# test2.net
KiCad netlist of a schematic drawn in EAGLE
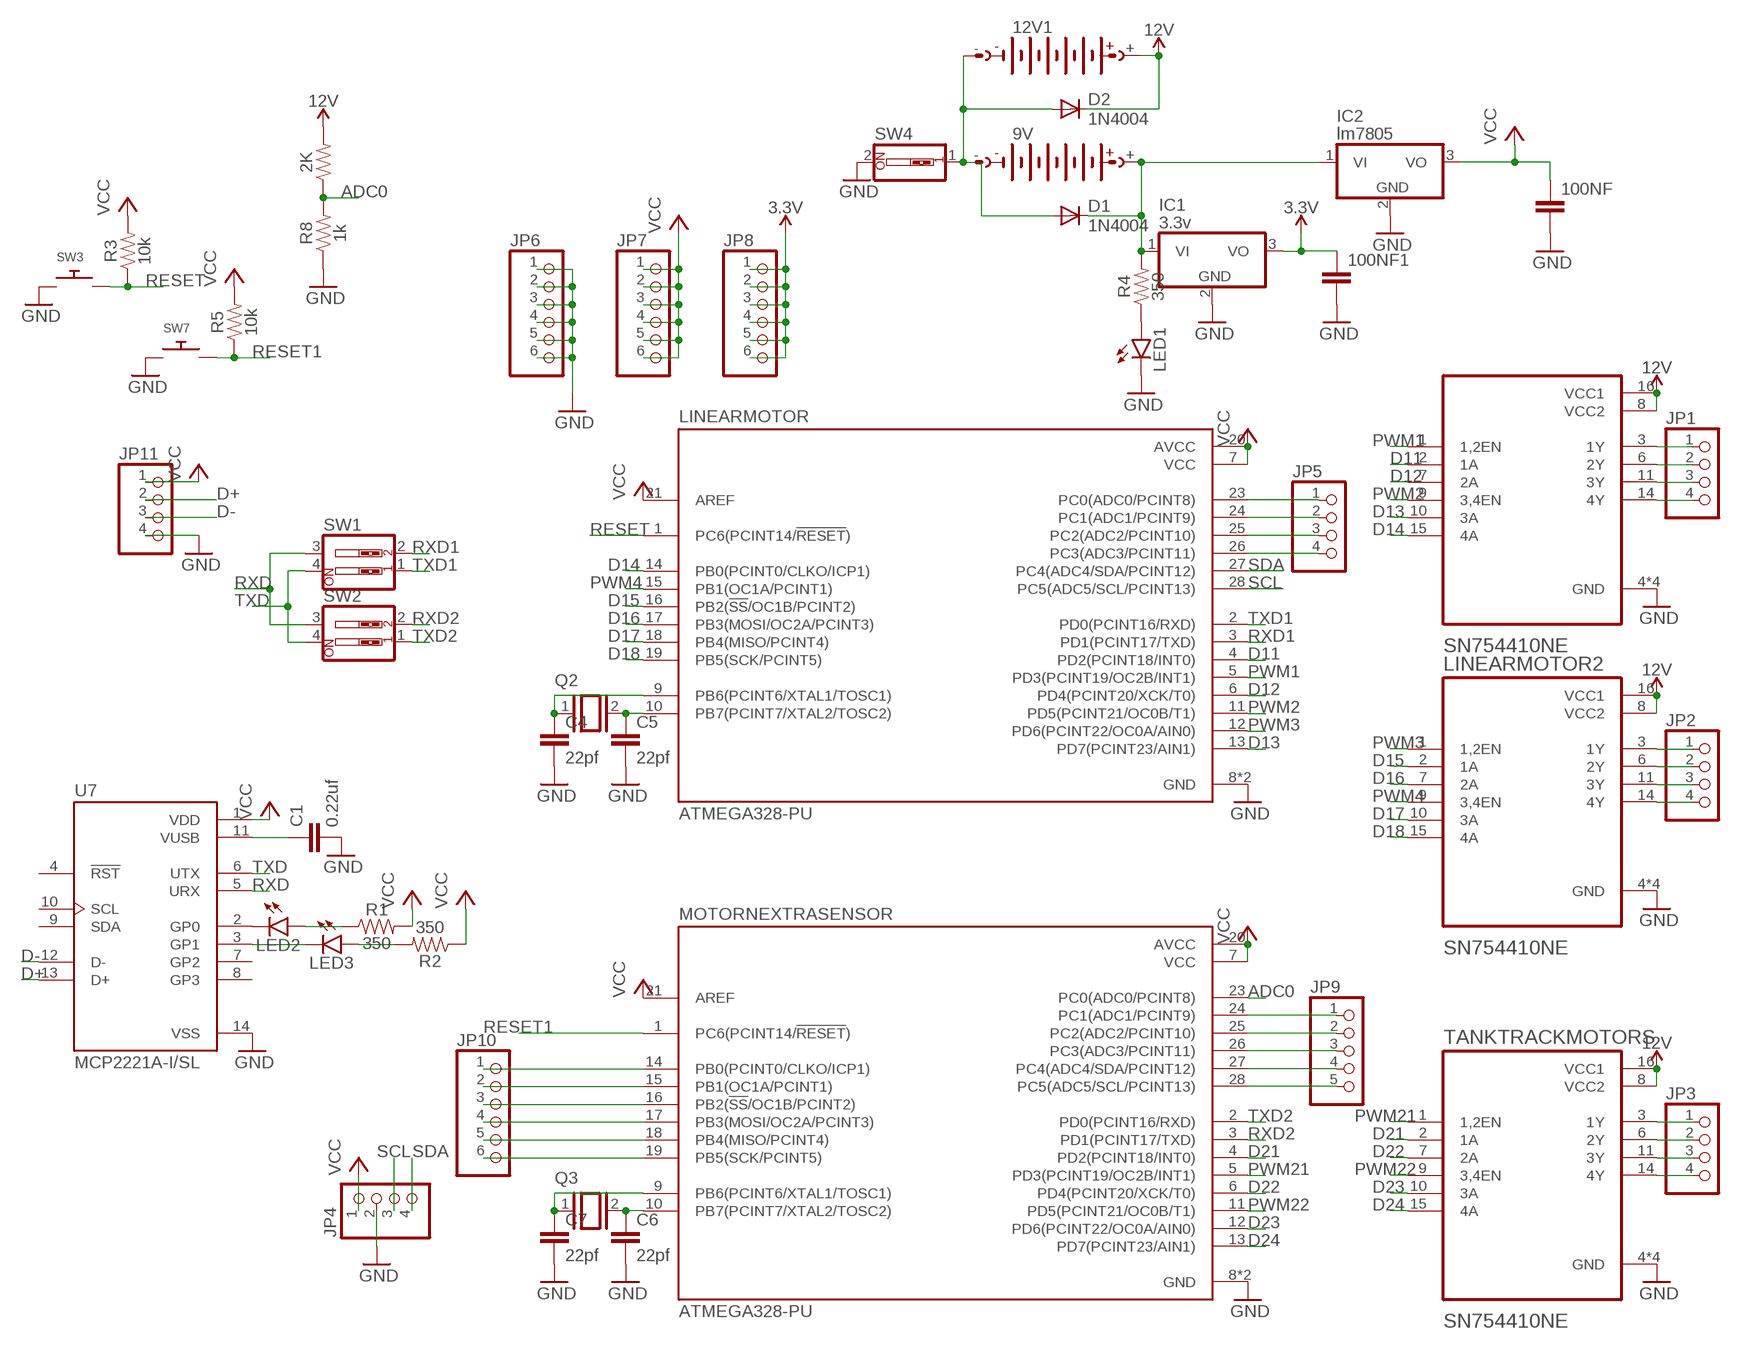
[diagram p0: schematic, sheet 1]

(export (version "E")
  (design (tool "Eeschema 10.0.6"))
  (components
    (comp (ref "2K")
      (value "2k")
      (footprint "eagle-import:AXIAL-0.3")
      (libsource (lib "eagle-import") (part "1KOHM-HORIZ-1/4W-1%"))
    )
    (comp (ref "9V")
      (value "AB9V")
      (footprint "eagle-import:AB9V")
      (libsource (lib "eagle-import") (part "AB9V"))
    )
    (comp (ref "12V1")
      (value "AB9V")
      (footprint "eagle-import:AB9V")
      (libsource (lib "eagle-import") (part "AB9V"))
    )
    (comp (ref "100NF")
      (value "330nF")
      (footprint "eagle-import:CAP-PTH-10MM")
      (libsource (lib "eagle-import") (part "10NF-PTH-10MM-10000V-1-%"))
    )
    (comp (ref "100NF1")
      (value "330nF")
      (footprint "eagle-import:CAP-PTH-10MM")
      (libsource (lib "eagle-import") (part "10NF-PTH-10MM-10000V-1-%"))
    )
    (comp (ref "C1")
      (value "0.22uf")
      (footprint "eagle-import:CAP-PTH-10MM")
      (libsource (lib "eagle-import") (part "10NF-PTH-10MM-10000V-1-%"))
    )
    (comp (ref "C4")
      (value "22pf")
      (footprint "eagle-import:CAP-PTH-10MM")
      (libsource (lib "eagle-import") (part "10NF-PTH-10MM-10000V-1-%"))
    )
    (comp (ref "C5")
      (value "22pf")
      (footprint "eagle-import:CAP-PTH-10MM")
      (libsource (lib "eagle-import") (part "10NF-PTH-10MM-10000V-1-%"))
    )
    (comp (ref "C6")
      (value "22pf")
      (footprint "eagle-import:CAP-PTH-10MM")
      (libsource (lib "eagle-import") (part "10NF-PTH-10MM-10000V-1-%"))
    )
    (comp (ref "C7")
      (value "22pf")
      (footprint "eagle-import:CAP-PTH-10MM")
      (libsource (lib "eagle-import") (part "10NF-PTH-10MM-10000V-1-%"))
    )
    (comp (ref "D1")
      (value "1N4004")
      (footprint "eagle-import:DO41-10")
      (libsource (lib "eagle-import") (part "1N4004"))
    )
    (comp (ref "D2")
      (value "1N4004")
      (footprint "eagle-import:DO41-10")
      (libsource (lib "eagle-import") (part "1N4004"))
    )
    (comp (ref "IC1")
      (value "3.3v")
      (footprint "eagle-import:TO220V")
      (libsource (lib "eagle-import") (part "78TV8"))
    )
    (comp (ref "IC2")
      (value "lm7805")
      (footprint "eagle-import:TO220V")
      (libsource (lib "eagle-import") (part "78TV8"))
    )
    (comp (ref "JP1")
      (value "PINHD-1X4")
      (footprint "eagle-import:1X04")
      (libsource (lib "eagle-import") (part "PINHD-1X4"))
    )
    (comp (ref "JP2")
      (value "PINHD-1X4")
      (footprint "eagle-import:1X04")
      (libsource (lib "eagle-import") (part "PINHD-1X4"))
    )
    (comp (ref "JP3")
      (value "PINHD-1X4")
      (footprint "eagle-import:1X04")
      (libsource (lib "eagle-import") (part "PINHD-1X4"))
    )
    (comp (ref "JP4")
      (value "PINHD-1X4")
      (footprint "eagle-import:1X04")
      (libsource (lib "eagle-import") (part "PINHD-1X4"))
    )
    (comp (ref "JP5")
      (value "PINHD-1X4")
      (footprint "eagle-import:1X04")
      (libsource (lib "eagle-import") (part "PINHD-1X4"))
    )
    (comp (ref "JP6")
      (value "PINHD-1X6")
      (footprint "eagle-import:1X06")
      (libsource (lib "eagle-import") (part "PINHD-1X6"))
    )
    (comp (ref "JP7")
      (value "PINHD-1X6")
      (footprint "eagle-import:1X06")
      (libsource (lib "eagle-import") (part "PINHD-1X6"))
    )
    (comp (ref "JP8")
      (value "PINHD-1X6")
      (footprint "eagle-import:1X06")
      (libsource (lib "eagle-import") (part "PINHD-1X6"))
    )
    (comp (ref "JP9")
      (value "PINHD-1X5")
      (footprint "eagle-import:1X05")
      (libsource (lib "eagle-import") (part "PINHD-1X5"))
    )
    (comp (ref "JP10")
      (value "PINHD-1X6")
      (footprint "eagle-import:1X06")
      (libsource (lib "eagle-import") (part "PINHD-1X6"))
    )
    (comp (ref "JP11")
      (value "PINHD-1X4")
      (footprint "eagle-import:1X04")
      (libsource (lib "eagle-import") (part "PINHD-1X4"))
    )
    (comp (ref "LED1")
      (value "LED3MM")
      (footprint "eagle-import:LED3MM")
      (libsource (lib "eagle-import") (part "LED3MM"))
    )
    (comp (ref "LED2")
      (value "LED3MM")
      (footprint "eagle-import:LED3MM")
      (libsource (lib "eagle-import") (part "LED3MM"))
    )
    (comp (ref "LED3")
      (value "LED3MM")
      (footprint "eagle-import:LED3MM")
      (libsource (lib "eagle-import") (part "LED3MM"))
    )
    (comp (ref "LINEARMOTOR")
      (value "ATMEGA328-PU")
      (footprint "eagle-import:DIP787W46P254L3467H508Q28")
      (fields (field (name "MF") "Microchip Technology"))
      (libsource (lib "eagle-import") (part "ATMEGA328-PU"))
    )
    (comp (ref "LINEARMOTOR1")
      (value "SN754410NE")
      (footprint "eagle-import:DIP762W45P254L1980H508Q16")
      (fields (field (name "MF") "Texas Instruments"))
      (libsource (lib "eagle-import") (part "SN754410NE"))
    )
    (comp (ref "LINEARMOTOR2")
      (value "SN754410NE")
      (footprint "eagle-import:DIP762W45P254L1980H508Q16")
      (fields (field (name "MF") "Texas Instruments"))
      (libsource (lib "eagle-import") (part "SN754410NE"))
    )
    (comp (ref "MOTORNEXTRASENSOR")
      (value "ATMEGA328-PU")
      (footprint "eagle-import:DIP787W46P254L3467H508Q28")
      (fields (field (name "MF") "Microchip Technology"))
      (libsource (lib "eagle-import") (part "ATMEGA328-PU"))
    )
    (comp (ref "Q2")
      (value "XTAL/S")
      (footprint "eagle-import:QS")
      (libsource (lib "eagle-import") (part "XTAL/S"))
    )
    (comp (ref "Q3")
      (value "XTAL/S")
      (footprint "eagle-import:QS")
      (libsource (lib "eagle-import") (part "XTAL/S"))
    )
    (comp (ref "R1")
      (value "350")
      (footprint "eagle-import:AXIAL-0.3")
      (libsource (lib "eagle-import") (part "1KOHM-HORIZ-1/4W-1%"))
    )
    (comp (ref "R2")
      (value "350")
      (footprint "eagle-import:AXIAL-0.3")
      (libsource (lib "eagle-import") (part "1KOHM-HORIZ-1/4W-1%"))
    )
    (comp (ref "R3")
      (value "10k")
      (footprint "eagle-import:AXIAL-0.3")
      (libsource (lib "eagle-import") (part "10KOHM-HORIZ-1/4W-1%"))
    )
    (comp (ref "R4")
      (value "350")
      (footprint "eagle-import:AXIAL-0.3")
      (libsource (lib "eagle-import") (part "1KOHM-HORIZ-1/4W-1%"))
    )
    (comp (ref "R5")
      (value "10k")
      (footprint "eagle-import:AXIAL-0.3")
      (libsource (lib "eagle-import") (part "10KOHM-HORIZ-1/4W-1%"))
    )
    (comp (ref "R8")
      (value "1k")
      (footprint "eagle-import:AXIAL-0.3")
      (libsource (lib "eagle-import") (part "1KOHM-HORIZ-1/4W-1%"))
    )
    (comp (ref "SW1")
      (value "SW_DIP-2")
      (footprint "eagle-import:EDG-02")
      (libsource (lib "eagle-import") (part "SW_DIP-2"))
    )
    (comp (ref "SW2")
      (value "SW_DIP-2")
      (footprint "eagle-import:EDG-02")
      (libsource (lib "eagle-import") (part "SW_DIP-2"))
    )
    (comp (ref "SW3")
      (value "SWITCH_PUSHBUTTONEVQ-PE")
      (footprint "eagle-import:TACT_PANA-EVQ")
      (libsource (lib "eagle-import") (part "SWITCH_PUSHBUTTONEVQ-PE"))
    )
    (comp (ref "SW4")
      (value "SW_DIP-1")
      (footprint "eagle-import:EDG-01")
      (libsource (lib "eagle-import") (part "SW_DIP-1"))
    )
    (comp (ref "SW7")
      (value "SWITCH_PUSHBUTTONEVQ-PE")
      (footprint "eagle-import:TACT_PANA-EVQ")
      (libsource (lib "eagle-import") (part "SWITCH_PUSHBUTTONEVQ-PE"))
    )
    (comp (ref "TANKTRACKMOTORS")
      (value "SN754410NE")
      (footprint "eagle-import:DIP762W45P254L1980H508Q16")
      (fields (field (name "MF") "Texas Instruments"))
      (libsource (lib "eagle-import") (part "SN754410NE"))
    )
    (comp (ref "U7")
      (value "MCP2221A-I/SL")
      (footprint "eagle-import:SOIC127P600X175-14N")
      (fields (field (name "MF") "Microchip"))
      (libsource (lib "eagle-import") (part "MCP2221A-I/SL"))
    )
  )
  (nets
    (net (code "1") (name "/ADC0") (class "Default")
      (node (ref "2K") (pin "P$1") (pinfunction "1_P$1") (pintype "passive"))
      (node (ref "MOTORNEXTRASENSOR") (pin "23") (pinfunction "PC0(ADC0/PCINT8)_23") (pintype "bidirectional"))
      (node (ref "R8") (pin "P$2") (pinfunction "2_P$2") (pintype "passive"))
    )
    (net (code "2") (name "/D+") (class "Default")
      (node (ref "JP11") (pin "2") (pinfunction "2_2") (pintype "passive"))
      (node (ref "U7") (pin "13") (pinfunction "D+_13") (pintype "bidirectional"))
    )
    (net (code "3") (name "/D-") (class "Default")
      (node (ref "JP11") (pin "3") (pinfunction "3_3") (pintype "passive"))
      (node (ref "U7") (pin "12") (pinfunction "D-_12") (pintype "bidirectional"))
    )
    (net (code "4") (name "/D11") (class "Default")
      (node (ref "LINEARMOTOR") (pin "4") (pinfunction "PD2(PCINT18/INT0)_4") (pintype "bidirectional"))
      (node (ref "LINEARMOTOR1") (pin "2") (pinfunction "1A_2") (pintype "input"))
    )
    (net (code "5") (name "/D12") (class "Default")
      (node (ref "LINEARMOTOR") (pin "6") (pinfunction "PD4(PCINT20/XCK/T0)_6") (pintype "bidirectional"))
      (node (ref "LINEARMOTOR1") (pin "7") (pinfunction "2A_7") (pintype "input"))
    )
    (net (code "6") (name "/D13") (class "Default")
      (node (ref "LINEARMOTOR") (pin "13") (pinfunction "PD7(PCINT23/AIN1)_13") (pintype "bidirectional"))
      (node (ref "LINEARMOTOR1") (pin "10") (pinfunction "3A_10") (pintype "input"))
    )
    (net (code "7") (name "/D14") (class "Default")
      (node (ref "LINEARMOTOR") (pin "14") (pinfunction "PB0(PCINT0/CLKO/ICP1)_14") (pintype "bidirectional"))
      (node (ref "LINEARMOTOR1") (pin "15") (pinfunction "4A_15") (pintype "input"))
    )
    (net (code "8") (name "/D15") (class "Default")
      (node (ref "LINEARMOTOR") (pin "16") (pinfunction "PB2(~{SS}/OC1B/PCINT2)_16") (pintype "bidirectional"))
      (node (ref "LINEARMOTOR2") (pin "2") (pinfunction "1A_2") (pintype "input"))
    )
    (net (code "9") (name "/D16") (class "Default")
      (node (ref "LINEARMOTOR") (pin "17") (pinfunction "PB3(MOSI/OC2A/PCINT3)_17") (pintype "bidirectional"))
      (node (ref "LINEARMOTOR2") (pin "7") (pinfunction "2A_7") (pintype "input"))
    )
    (net (code "10") (name "/D17") (class "Default")
      (node (ref "LINEARMOTOR") (pin "18") (pinfunction "PB4(MISO/PCINT4)_18") (pintype "bidirectional"))
      (node (ref "LINEARMOTOR2") (pin "10") (pinfunction "3A_10") (pintype "input"))
    )
    (net (code "11") (name "/D18") (class "Default")
      (node (ref "LINEARMOTOR") (pin "19") (pinfunction "PB5(SCK/PCINT5)_19") (pintype "bidirectional"))
      (node (ref "LINEARMOTOR2") (pin "15") (pinfunction "4A_15") (pintype "input"))
    )
    (net (code "12") (name "/D21") (class "Default")
      (node (ref "MOTORNEXTRASENSOR") (pin "4") (pinfunction "PD2(PCINT18/INT0)_4") (pintype "bidirectional"))
      (node (ref "TANKTRACKMOTORS") (pin "2") (pinfunction "1A_2") (pintype "input"))
    )
    (net (code "13") (name "/D22") (class "Default")
      (node (ref "MOTORNEXTRASENSOR") (pin "6") (pinfunction "PD4(PCINT20/XCK/T0)_6") (pintype "bidirectional"))
      (node (ref "TANKTRACKMOTORS") (pin "7") (pinfunction "2A_7") (pintype "input"))
    )
    (net (code "14") (name "/D23") (class "Default")
      (node (ref "MOTORNEXTRASENSOR") (pin "12") (pinfunction "PD6(PCINT22/OC0A/AIN0)_12") (pintype "bidirectional"))
      (node (ref "TANKTRACKMOTORS") (pin "10") (pinfunction "3A_10") (pintype "input"))
    )
    (net (code "15") (name "/D24") (class "Default")
      (node (ref "MOTORNEXTRASENSOR") (pin "13") (pinfunction "PD7(PCINT23/AIN1)_13") (pintype "bidirectional"))
      (node (ref "TANKTRACKMOTORS") (pin "15") (pinfunction "4A_15") (pintype "input"))
    )
    (net (code "16") (name "/PWM1") (class "Default")
      (node (ref "LINEARMOTOR") (pin "5") (pinfunction "PD3(PCINT19/OC2B/INT1)_5") (pintype "bidirectional"))
      (node (ref "LINEARMOTOR1") (pin "1") (pinfunction "1,2EN_1") (pintype "input"))
    )
    (net (code "17") (name "/PWM2") (class "Default")
      (node (ref "LINEARMOTOR") (pin "11") (pinfunction "PD5(PCINT21/OC0B/T1)_11") (pintype "bidirectional"))
      (node (ref "LINEARMOTOR1") (pin "9") (pinfunction "3,4EN_9") (pintype "input"))
    )
    (net (code "18") (name "/PWM3") (class "Default")
      (node (ref "LINEARMOTOR") (pin "12") (pinfunction "PD6(PCINT22/OC0A/AIN0)_12") (pintype "bidirectional"))
      (node (ref "LINEARMOTOR2") (pin "1") (pinfunction "1,2EN_1") (pintype "input"))
    )
    (net (code "19") (name "/PWM4") (class "Default")
      (node (ref "LINEARMOTOR") (pin "15") (pinfunction "PB1(OC1A/PCINT1)_15") (pintype "bidirectional"))
      (node (ref "LINEARMOTOR2") (pin "9") (pinfunction "3,4EN_9") (pintype "input"))
    )
    (net (code "20") (name "/PWM21") (class "Default")
      (node (ref "MOTORNEXTRASENSOR") (pin "5") (pinfunction "PD3(PCINT19/OC2B/INT1)_5") (pintype "bidirectional"))
      (node (ref "TANKTRACKMOTORS") (pin "1") (pinfunction "1,2EN_1") (pintype "input"))
    )
    (net (code "21") (name "/PWM22") (class "Default")
      (node (ref "MOTORNEXTRASENSOR") (pin "11") (pinfunction "PD5(PCINT21/OC0B/T1)_11") (pintype "bidirectional"))
      (node (ref "TANKTRACKMOTORS") (pin "9") (pinfunction "3,4EN_9") (pintype "input"))
    )
    (net (code "22") (name "/RESET") (class "Default")
      (node (ref "LINEARMOTOR") (pin "1") (pinfunction "PC6(PCINT14/~{RESET})_1") (pintype "bidirectional"))
      (node (ref "R3") (pin "P$1") (pinfunction "1_P$1") (pintype "passive"))
      (node (ref "SW3") (pin "P$2") (pinfunction "P$2_P$2") (pintype "passive"))
    )
    (net (code "23") (name "/RESET1") (class "Default")
      (node (ref "MOTORNEXTRASENSOR") (pin "1") (pinfunction "PC6(PCINT14/~{RESET})_1") (pintype "bidirectional"))
      (node (ref "R5") (pin "P$1") (pinfunction "1_P$1") (pintype "passive"))
      (node (ref "SW7") (pin "P$2") (pinfunction "P$2_P$2") (pintype "passive"))
    )
    (net (code "24") (name "/RXD") (class "Default")
      (node (ref "SW1") (pin "3") (pinfunction "3_3") (pintype "passive"))
      (node (ref "SW2") (pin "3") (pinfunction "3_3") (pintype "passive"))
      (node (ref "U7") (pin "5") (pinfunction "URX_5") (pintype "input"))
    )
    (net (code "25") (name "/RXD1") (class "Default")
      (node (ref "LINEARMOTOR") (pin "3") (pinfunction "PD1(PCINT17/TXD)_3") (pintype "bidirectional"))
      (node (ref "SW1") (pin "2") (pinfunction "2_2") (pintype "passive"))
    )
    (net (code "26") (name "/RXD2") (class "Default")
      (node (ref "MOTORNEXTRASENSOR") (pin "3") (pinfunction "PD1(PCINT17/TXD)_3") (pintype "bidirectional"))
      (node (ref "SW2") (pin "2") (pinfunction "2_2") (pintype "passive"))
    )
    (net (code "27") (name "/SCL") (class "Default")
      (node (ref "JP4") (pin "3") (pinfunction "3_3") (pintype "passive"))
      (node (ref "LINEARMOTOR") (pin "28") (pinfunction "PC5(ADC5/SCL/PCINT13)_28") (pintype "bidirectional"))
    )
    (net (code "28") (name "/SDA") (class "Default")
      (node (ref "JP4") (pin "4") (pinfunction "4_4") (pintype "passive"))
      (node (ref "LINEARMOTOR") (pin "27") (pinfunction "PC4(ADC4/SDA/PCINT12)_27") (pintype "bidirectional"))
    )
    (net (code "29") (name "/TXD") (class "Default")
      (node (ref "SW1") (pin "4") (pinfunction "4_4") (pintype "passive"))
      (node (ref "SW2") (pin "4") (pinfunction "4_4") (pintype "passive"))
      (node (ref "U7") (pin "6") (pinfunction "UTX_6") (pintype "output"))
    )
    (net (code "30") (name "/TXD1") (class "Default")
      (node (ref "LINEARMOTOR") (pin "2") (pinfunction "PD0(PCINT16/RXD)_2") (pintype "bidirectional"))
      (node (ref "SW1") (pin "1") (pinfunction "1_1") (pintype "passive"))
    )
    (net (code "31") (name "/TXD2") (class "Default")
      (node (ref "MOTORNEXTRASENSOR") (pin "2") (pinfunction "PD0(PCINT16/RXD)_2") (pintype "bidirectional"))
      (node (ref "SW2") (pin "1") (pinfunction "1_1") (pintype "passive"))
    )
    (net (code "32") (name "3.3V") (class "Default")
      (node (ref "100NF1") (pin "1") (pinfunction "1_1") (pintype "passive"))
      (node (ref "IC1") (pin "3") (pinfunction "VO_3") (pintype "passive"))
      (node (ref "JP8") (pin "1") (pinfunction "1_1") (pintype "passive"))
      (node (ref "JP8") (pin "2") (pinfunction "2_2") (pintype "passive"))
      (node (ref "JP8") (pin "3") (pinfunction "3_3") (pintype "passive"))
      (node (ref "JP8") (pin "4") (pinfunction "4_4") (pintype "passive"))
      (node (ref "JP8") (pin "5") (pinfunction "5_5") (pintype "passive"))
      (node (ref "JP8") (pin "6") (pinfunction "6_6") (pintype "passive"))
    )
    (net (code "33") (name "12V") (class "Default")
      (node (ref "12V1") (pin "+") (pinfunction "+_+") (pintype "passive"))
      (node (ref "2K") (pin "P$2") (pinfunction "2_P$2") (pintype "passive"))
      (node (ref "D2") (pin "C") (pinfunction "C_C") (pintype "passive"))
      (node (ref "LINEARMOTOR1") (pin "16") (pinfunction "VCC1_16") (pintype "power_in"))
      (node (ref "LINEARMOTOR1") (pin "8") (pinfunction "VCC2_8") (pintype "power_in"))
      (node (ref "LINEARMOTOR2") (pin "16") (pinfunction "VCC1_16") (pintype "power_in"))
      (node (ref "LINEARMOTOR2") (pin "8") (pinfunction "VCC2_8") (pintype "power_in"))
      (node (ref "TANKTRACKMOTORS") (pin "16") (pinfunction "VCC1_16") (pintype "power_in"))
      (node (ref "TANKTRACKMOTORS") (pin "8") (pinfunction "VCC2_8") (pintype "power_in"))
    )
    (net (code "34") (name "GND") (class "Default")
      (node (ref "100NF") (pin "2") (pinfunction "2_2") (pintype "passive"))
      (node (ref "100NF1") (pin "2") (pinfunction "2_2") (pintype "passive"))
      (node (ref "C1") (pin "2") (pinfunction "2_2") (pintype "passive"))
      (node (ref "C4") (pin "2") (pinfunction "2_2") (pintype "passive"))
      (node (ref "C5") (pin "2") (pinfunction "2_2") (pintype "passive"))
      (node (ref "C6") (pin "2") (pinfunction "2_2") (pintype "passive"))
      (node (ref "C7") (pin "2") (pinfunction "2_2") (pintype "passive"))
      (node (ref "IC1") (pin "2") (pinfunction "GND_2") (pintype "passive"))
      (node (ref "IC2") (pin "2") (pinfunction "GND_2") (pintype "passive"))
      (node (ref "JP11") (pin "4") (pinfunction "4_4") (pintype "passive"))
      (node (ref "JP4") (pin "2") (pinfunction "2_2") (pintype "passive"))
      (node (ref "JP6") (pin "1") (pinfunction "1_1") (pintype "passive"))
      (node (ref "JP6") (pin "2") (pinfunction "2_2") (pintype "passive"))
      (node (ref "JP6") (pin "3") (pinfunction "3_3") (pintype "passive"))
      (node (ref "JP6") (pin "4") (pinfunction "4_4") (pintype "passive"))
      (node (ref "JP6") (pin "5") (pinfunction "5_5") (pintype "passive"))
      (node (ref "JP6") (pin "6") (pinfunction "6_6") (pintype "passive"))
      (node (ref "LED1") (pin "K") (pinfunction "C_K") (pintype "passive"))
      (node (ref "LINEARMOTOR") (pin "22") (pinfunction "GND_22") (pintype "power_in"))
      (node (ref "LINEARMOTOR") (pin "8") (pinfunction "GND_8") (pintype "power_in"))
      (node (ref "LINEARMOTOR1") (pin "12") (pinfunction "GND_12") (pintype "power_in"))
      (node (ref "LINEARMOTOR1") (pin "13") (pinfunction "GND_13") (pintype "power_in"))
      (node (ref "LINEARMOTOR1") (pin "4") (pinfunction "GND_4") (pintype "power_in"))
      (node (ref "LINEARMOTOR1") (pin "5") (pinfunction "GND_5") (pintype "power_in"))
      (node (ref "LINEARMOTOR2") (pin "12") (pinfunction "GND_12") (pintype "power_in"))
      (node (ref "LINEARMOTOR2") (pin "13") (pinfunction "GND_13") (pintype "power_in"))
      (node (ref "LINEARMOTOR2") (pin "4") (pinfunction "GND_4") (pintype "power_in"))
      (node (ref "LINEARMOTOR2") (pin "5") (pinfunction "GND_5") (pintype "power_in"))
      (node (ref "MOTORNEXTRASENSOR") (pin "22") (pinfunction "GND_22") (pintype "power_in"))
      (node (ref "MOTORNEXTRASENSOR") (pin "8") (pinfunction "GND_8") (pintype "power_in"))
      (node (ref "R8") (pin "P$1") (pinfunction "1_P$1") (pintype "passive"))
      (node (ref "SW3") (pin "P$1") (pinfunction "P$1_P$1") (pintype "passive"))
      (node (ref "SW4") (pin "2") (pinfunction "2_2") (pintype "passive"))
      (node (ref "SW7") (pin "P$1") (pinfunction "P$1_P$1") (pintype "passive"))
      (node (ref "TANKTRACKMOTORS") (pin "12") (pinfunction "GND_12") (pintype "power_in"))
      (node (ref "TANKTRACKMOTORS") (pin "13") (pinfunction "GND_13") (pintype "power_in"))
      (node (ref "TANKTRACKMOTORS") (pin "4") (pinfunction "GND_4") (pintype "power_in"))
      (node (ref "TANKTRACKMOTORS") (pin "5") (pinfunction "GND_5") (pintype "power_in"))
      (node (ref "U7") (pin "14") (pinfunction "VSS_14") (pintype "power_in"))
    )
    (net (code "35") (name "Net-(12V1-Pad-)") (class "Default")
      (node (ref "12V1") (pin "-") (pinfunction "-_-") (pintype "passive"))
      (node (ref "9V") (pin "-") (pinfunction "-_-") (pintype "passive"))
      (node (ref "D1") (pin "A") (pinfunction "A_A") (pintype "passive"))
      (node (ref "D2") (pin "A") (pinfunction "A_A") (pintype "passive"))
      (node (ref "SW4") (pin "1") (pinfunction "1_1") (pintype "passive"))
    )
    (net (code "36") (name "Net-(IC1-VI)") (class "Default")
      (node (ref "9V") (pin "+") (pinfunction "+_+") (pintype "passive"))
      (node (ref "D1") (pin "C") (pinfunction "C_C") (pintype "passive"))
      (node (ref "IC1") (pin "1") (pinfunction "VI_1") (pintype "input"))
      (node (ref "IC2") (pin "1") (pinfunction "VI_1") (pintype "input"))
      (node (ref "R4") (pin "P$2") (pinfunction "2_P$2") (pintype "passive"))
    )
    (net (code "37") (name "Net-(LED2-C)") (class "Default")
      (node (ref "LED2") (pin "K") (pinfunction "C_K") (pintype "passive"))
      (node (ref "U7") (pin "2") (pinfunction "GP0_2") (pintype "bidirectional"))
    )
    (net (code "38") (name "Net-(LED3-C)") (class "Default")
      (node (ref "LED3") (pin "K") (pinfunction "C_K") (pintype "passive"))
      (node (ref "U7") (pin "3") (pinfunction "GP1_3") (pintype "bidirectional"))
    )
    (net (code "39") (name "Net-(LINEARMOTOR-PB6(PCINT6{slash}XTAL1{slash}TOSC1))") (class "Default")
      (node (ref "C4") (pin "1") (pinfunction "1_1") (pintype "passive"))
      (node (ref "LINEARMOTOR") (pin "9") (pinfunction "PB6(PCINT6/XTAL1/TOSC1)_9") (pintype "bidirectional"))
      (node (ref "Q2") (pin "1") (pinfunction "1_1") (pintype "passive"))
    )
    (net (code "40") (name "Net-(LINEARMOTOR-PB7(PCINT7{slash}XTAL2{slash}TOSC2))") (class "Default")
      (node (ref "C5") (pin "1") (pinfunction "1_1") (pintype "passive"))
      (node (ref "LINEARMOTOR") (pin "10") (pinfunction "PB7(PCINT7/XTAL2/TOSC2)_10") (pintype "bidirectional"))
      (node (ref "Q2") (pin "2") (pinfunction "2_2") (pintype "passive"))
    )
    (net (code "41") (name "Net-(LINEARMOTOR-PC0(ADC0{slash}PCINT8))") (class "Default")
      (node (ref "JP5") (pin "1") (pinfunction "1_1") (pintype "passive"))
      (node (ref "LINEARMOTOR") (pin "23") (pinfunction "PC0(ADC0/PCINT8)_23") (pintype "bidirectional"))
    )
    (net (code "42") (name "Net-(LINEARMOTOR-PC1(ADC1{slash}PCINT9))") (class "Default")
      (node (ref "JP5") (pin "2") (pinfunction "2_2") (pintype "passive"))
      (node (ref "LINEARMOTOR") (pin "24") (pinfunction "PC1(ADC1/PCINT9)_24") (pintype "bidirectional"))
    )
    (net (code "43") (name "Net-(LINEARMOTOR-PC2(ADC2{slash}PCINT10))") (class "Default")
      (node (ref "JP5") (pin "3") (pinfunction "3_3") (pintype "passive"))
      (node (ref "LINEARMOTOR") (pin "25") (pinfunction "PC2(ADC2/PCINT10)_25") (pintype "bidirectional"))
    )
    (net (code "44") (name "Net-(LINEARMOTOR-PC3(ADC3{slash}PCINT11))") (class "Default")
      (node (ref "JP5") (pin "4") (pinfunction "4_4") (pintype "passive"))
      (node (ref "LINEARMOTOR") (pin "26") (pinfunction "PC3(ADC3/PCINT11)_26") (pintype "bidirectional"))
    )
    (net (code "45") (name "Net-(LINEARMOTOR1-1Y)") (class "Default")
      (node (ref "JP1") (pin "1") (pinfunction "1_1") (pintype "passive"))
      (node (ref "LINEARMOTOR1") (pin "3") (pinfunction "1Y_3") (pintype "output"))
    )
    (net (code "46") (name "Net-(LINEARMOTOR1-2Y)") (class "Default")
      (node (ref "JP1") (pin "2") (pinfunction "2_2") (pintype "passive"))
      (node (ref "LINEARMOTOR1") (pin "6") (pinfunction "2Y_6") (pintype "output"))
    )
    (net (code "47") (name "Net-(LINEARMOTOR1-3Y)") (class "Default")
      (node (ref "JP1") (pin "3") (pinfunction "3_3") (pintype "passive"))
      (node (ref "LINEARMOTOR1") (pin "11") (pinfunction "3Y_11") (pintype "output"))
    )
    (net (code "48") (name "Net-(LINEARMOTOR1-4Y)") (class "Default")
      (node (ref "JP1") (pin "4") (pinfunction "4_4") (pintype "passive"))
      (node (ref "LINEARMOTOR1") (pin "14") (pinfunction "4Y_14") (pintype "output"))
    )
    (net (code "49") (name "Net-(LINEARMOTOR2-1Y)") (class "Default")
      (node (ref "JP2") (pin "1") (pinfunction "1_1") (pintype "passive"))
      (node (ref "LINEARMOTOR2") (pin "3") (pinfunction "1Y_3") (pintype "output"))
    )
    (net (code "50") (name "Net-(LINEARMOTOR2-2Y)") (class "Default")
      (node (ref "JP2") (pin "2") (pinfunction "2_2") (pintype "passive"))
      (node (ref "LINEARMOTOR2") (pin "6") (pinfunction "2Y_6") (pintype "output"))
    )
    (net (code "51") (name "Net-(LINEARMOTOR2-3Y)") (class "Default")
      (node (ref "JP2") (pin "3") (pinfunction "3_3") (pintype "passive"))
      (node (ref "LINEARMOTOR2") (pin "11") (pinfunction "3Y_11") (pintype "output"))
    )
    (net (code "52") (name "Net-(LINEARMOTOR2-4Y)") (class "Default")
      (node (ref "JP2") (pin "4") (pinfunction "4_4") (pintype "passive"))
      (node (ref "LINEARMOTOR2") (pin "14") (pinfunction "4Y_14") (pintype "output"))
    )
    (net (code "53") (name "Net-(MOTORNEXTRASENSOR-PB0(PCINT0{slash}CLKO{slash}ICP1))") (class "Default")
      (node (ref "JP10") (pin "1") (pinfunction "1_1") (pintype "passive"))
      (node (ref "MOTORNEXTRASENSOR") (pin "14") (pinfunction "PB0(PCINT0/CLKO/ICP1)_14") (pintype "bidirectional"))
    )
    (net (code "54") (name "Net-(MOTORNEXTRASENSOR-PB1(OC1A{slash}PCINT1))") (class "Default")
      (node (ref "JP10") (pin "2") (pinfunction "2_2") (pintype "passive"))
      (node (ref "MOTORNEXTRASENSOR") (pin "15") (pinfunction "PB1(OC1A/PCINT1)_15") (pintype "bidirectional"))
    )
    (net (code "55") (name "Net-(MOTORNEXTRASENSOR-PB2(~{SS}{slash}OC1B{slash}PCINT2))") (class "Default")
      (node (ref "JP10") (pin "3") (pinfunction "3_3") (pintype "passive"))
      (node (ref "MOTORNEXTRASENSOR") (pin "16") (pinfunction "PB2(~{SS}/OC1B/PCINT2)_16") (pintype "bidirectional"))
    )
    (net (code "56") (name "Net-(MOTORNEXTRASENSOR-PB3(MOSI{slash}OC2A{slash}PCINT3))") (class "Default")
      (node (ref "JP10") (pin "4") (pinfunction "4_4") (pintype "passive"))
      (node (ref "MOTORNEXTRASENSOR") (pin "17") (pinfunction "PB3(MOSI/OC2A/PCINT3)_17") (pintype "bidirectional"))
    )
    (net (code "57") (name "Net-(MOTORNEXTRASENSOR-PB4(MISO{slash}PCINT4))") (class "Default")
      (node (ref "JP10") (pin "5") (pinfunction "5_5") (pintype "passive"))
      (node (ref "MOTORNEXTRASENSOR") (pin "18") (pinfunction "PB4(MISO/PCINT4)_18") (pintype "bidirectional"))
    )
    (net (code "58") (name "Net-(MOTORNEXTRASENSOR-PB5(SCK{slash}PCINT5))") (class "Default")
      (node (ref "JP10") (pin "6") (pinfunction "6_6") (pintype "passive"))
      (node (ref "MOTORNEXTRASENSOR") (pin "19") (pinfunction "PB5(SCK/PCINT5)_19") (pintype "bidirectional"))
    )
    (net (code "59") (name "Net-(MOTORNEXTRASENSOR-PB6(PCINT6{slash}XTAL1{slash}TOSC1))") (class "Default")
      (node (ref "C7") (pin "1") (pinfunction "1_1") (pintype "passive"))
      (node (ref "MOTORNEXTRASENSOR") (pin "9") (pinfunction "PB6(PCINT6/XTAL1/TOSC1)_9") (pintype "bidirectional"))
      (node (ref "Q3") (pin "1") (pinfunction "1_1") (pintype "passive"))
    )
    (net (code "60") (name "Net-(MOTORNEXTRASENSOR-PB7(PCINT7{slash}XTAL2{slash}TOSC2))") (class "Default")
      (node (ref "C6") (pin "1") (pinfunction "1_1") (pintype "passive"))
      (node (ref "MOTORNEXTRASENSOR") (pin "10") (pinfunction "PB7(PCINT7/XTAL2/TOSC2)_10") (pintype "bidirectional"))
      (node (ref "Q3") (pin "2") (pinfunction "2_2") (pintype "passive"))
    )
    (net (code "61") (name "Net-(MOTORNEXTRASENSOR-PC1(ADC1{slash}PCINT9))") (class "Default")
      (node (ref "JP9") (pin "1") (pinfunction "1_1") (pintype "passive"))
      (node (ref "MOTORNEXTRASENSOR") (pin "24") (pinfunction "PC1(ADC1/PCINT9)_24") (pintype "bidirectional"))
    )
    (net (code "62") (name "Net-(MOTORNEXTRASENSOR-PC2(ADC2{slash}PCINT10))") (class "Default")
      (node (ref "JP9") (pin "2") (pinfunction "2_2") (pintype "passive"))
      (node (ref "MOTORNEXTRASENSOR") (pin "25") (pinfunction "PC2(ADC2/PCINT10)_25") (pintype "bidirectional"))
    )
    (net (code "63") (name "Net-(MOTORNEXTRASENSOR-PC3(ADC3{slash}PCINT11))") (class "Default")
      (node (ref "JP9") (pin "3") (pinfunction "3_3") (pintype "passive"))
      (node (ref "MOTORNEXTRASENSOR") (pin "26") (pinfunction "PC3(ADC3/PCINT11)_26") (pintype "bidirectional"))
    )
    (net (code "64") (name "Net-(MOTORNEXTRASENSOR-PC4(ADC4{slash}SDA{slash}PCINT12))") (class "Default")
      (node (ref "JP9") (pin "4") (pinfunction "4_4") (pintype "passive"))
      (node (ref "MOTORNEXTRASENSOR") (pin "27") (pinfunction "PC4(ADC4/SDA/PCINT12)_27") (pintype "bidirectional"))
    )
    (net (code "65") (name "Net-(MOTORNEXTRASENSOR-PC5(ADC5{slash}SCL{slash}PCINT13))") (class "Default")
      (node (ref "JP9") (pin "5") (pinfunction "5_5") (pintype "passive"))
      (node (ref "MOTORNEXTRASENSOR") (pin "28") (pinfunction "PC5(ADC5/SCL/PCINT13)_28") (pintype "bidirectional"))
    )
    (net (code "66") (name "Net-(R1-1)") (class "Default")
      (node (ref "LED2") (pin "A") (pinfunction "A_A") (pintype "passive"))
      (node (ref "R1") (pin "P$1") (pinfunction "1_P$1") (pintype "passive"))
    )
    (net (code "67") (name "Net-(R2-2)") (class "Default")
      (node (ref "LED3") (pin "A") (pinfunction "A_A") (pintype "passive"))
      (node (ref "R2") (pin "P$2") (pinfunction "2_P$2") (pintype "passive"))
    )
    (net (code "68") (name "Net-(R4-1)") (class "Default")
      (node (ref "LED1") (pin "A") (pinfunction "A_A") (pintype "passive"))
      (node (ref "R4") (pin "P$1") (pinfunction "1_P$1") (pintype "passive"))
    )
    (net (code "69") (name "Net-(TANKTRACKMOTORS-1Y)") (class "Default")
      (node (ref "JP3") (pin "1") (pinfunction "1_1") (pintype "passive"))
      (node (ref "TANKTRACKMOTORS") (pin "3") (pinfunction "1Y_3") (pintype "output"))
    )
    (net (code "70") (name "Net-(TANKTRACKMOTORS-2Y)") (class "Default")
      (node (ref "JP3") (pin "2") (pinfunction "2_2") (pintype "passive"))
      (node (ref "TANKTRACKMOTORS") (pin "6") (pinfunction "2Y_6") (pintype "output"))
    )
    (net (code "71") (name "Net-(TANKTRACKMOTORS-3Y)") (class "Default")
      (node (ref "JP3") (pin "3") (pinfunction "3_3") (pintype "passive"))
      (node (ref "TANKTRACKMOTORS") (pin "11") (pinfunction "3Y_11") (pintype "output"))
    )
    (net (code "72") (name "Net-(TANKTRACKMOTORS-4Y)") (class "Default")
      (node (ref "JP3") (pin "4") (pinfunction "4_4") (pintype "passive"))
      (node (ref "TANKTRACKMOTORS") (pin "14") (pinfunction "4Y_14") (pintype "output"))
    )
    (net (code "73") (name "Net-(U7-VUSB)") (class "Default")
      (node (ref "C1") (pin "1") (pinfunction "1_1") (pintype "passive"))
      (node (ref "U7") (pin "11") (pinfunction "VUSB_11") (pintype "power_in"))
    )
    (net (code "74") (name "VCC") (class "Default")
      (node (ref "100NF") (pin "1") (pinfunction "1_1") (pintype "passive"))
      (node (ref "IC2") (pin "3") (pinfunction "VO_3") (pintype "passive"))
      (node (ref "JP11") (pin "1") (pinfunction "1_1") (pintype "passive"))
      (node (ref "JP4") (pin "1") (pinfunction "1_1") (pintype "passive"))
      (node (ref "JP7") (pin "1") (pinfunction "1_1") (pintype "passive"))
      (node (ref "JP7") (pin "2") (pinfunction "2_2") (pintype "passive"))
      (node (ref "JP7") (pin "3") (pinfunction "3_3") (pintype "passive"))
      (node (ref "JP7") (pin "4") (pinfunction "4_4") (pintype "passive"))
      (node (ref "JP7") (pin "5") (pinfunction "5_5") (pintype "passive"))
      (node (ref "JP7") (pin "6") (pinfunction "6_6") (pintype "passive"))
      (node (ref "LINEARMOTOR") (pin "20") (pinfunction "AVCC_20") (pintype "power_in"))
      (node (ref "LINEARMOTOR") (pin "21") (pinfunction "AREF_21") (pintype "input"))
      (node (ref "LINEARMOTOR") (pin "7") (pinfunction "VCC_7") (pintype "power_in"))
      (node (ref "MOTORNEXTRASENSOR") (pin "20") (pinfunction "AVCC_20") (pintype "power_in"))
      (node (ref "MOTORNEXTRASENSOR") (pin "21") (pinfunction "AREF_21") (pintype "input"))
      (node (ref "MOTORNEXTRASENSOR") (pin "7") (pinfunction "VCC_7") (pintype "power_in"))
      (node (ref "R1") (pin "P$2") (pinfunction "2_P$2") (pintype "passive"))
      (node (ref "R2") (pin "P$1") (pinfunction "1_P$1") (pintype "passive"))
      (node (ref "R3") (pin "P$2") (pinfunction "2_P$2") (pintype "passive"))
      (node (ref "R5") (pin "P$2") (pinfunction "2_P$2") (pintype "passive"))
      (node (ref "U7") (pin "1") (pinfunction "VDD_1") (pintype "power_in"))
    )
    (net (code "75") (name "unconnected-(U7-GP2-Pad7)") (class "Default")
      (node (ref "U7") (pin "7") (pinfunction "GP2_7") (pintype "bidirectional"))
    )
    (net (code "76") (name "unconnected-(U7-GP3-Pad8)") (class "Default")
      (node (ref "U7") (pin "8") (pinfunction "GP3_8") (pintype "bidirectional"))
    )
    (net (code "77") (name "unconnected-(U7-SCL-Pad10)") (class "Default")
      (node (ref "U7") (pin "10") (pinfunction "SCL_10") (pintype "bidirectional"))
    )
    (net (code "78") (name "unconnected-(U7-SDA-Pad9)") (class "Default")
      (node (ref "U7") (pin "9") (pinfunction "SDA_9") (pintype "bidirectional"))
    )
    (net (code "79") (name "unconnected-(U7-~{RST}-Pad4)") (class "Default")
      (node (ref "U7") (pin "4") (pinfunction "~{RST}_4") (pintype "input"))
    )
  )
)
